# BSPD_SMD.net
KiCad netlist of a schematic drawn in Altium Designer
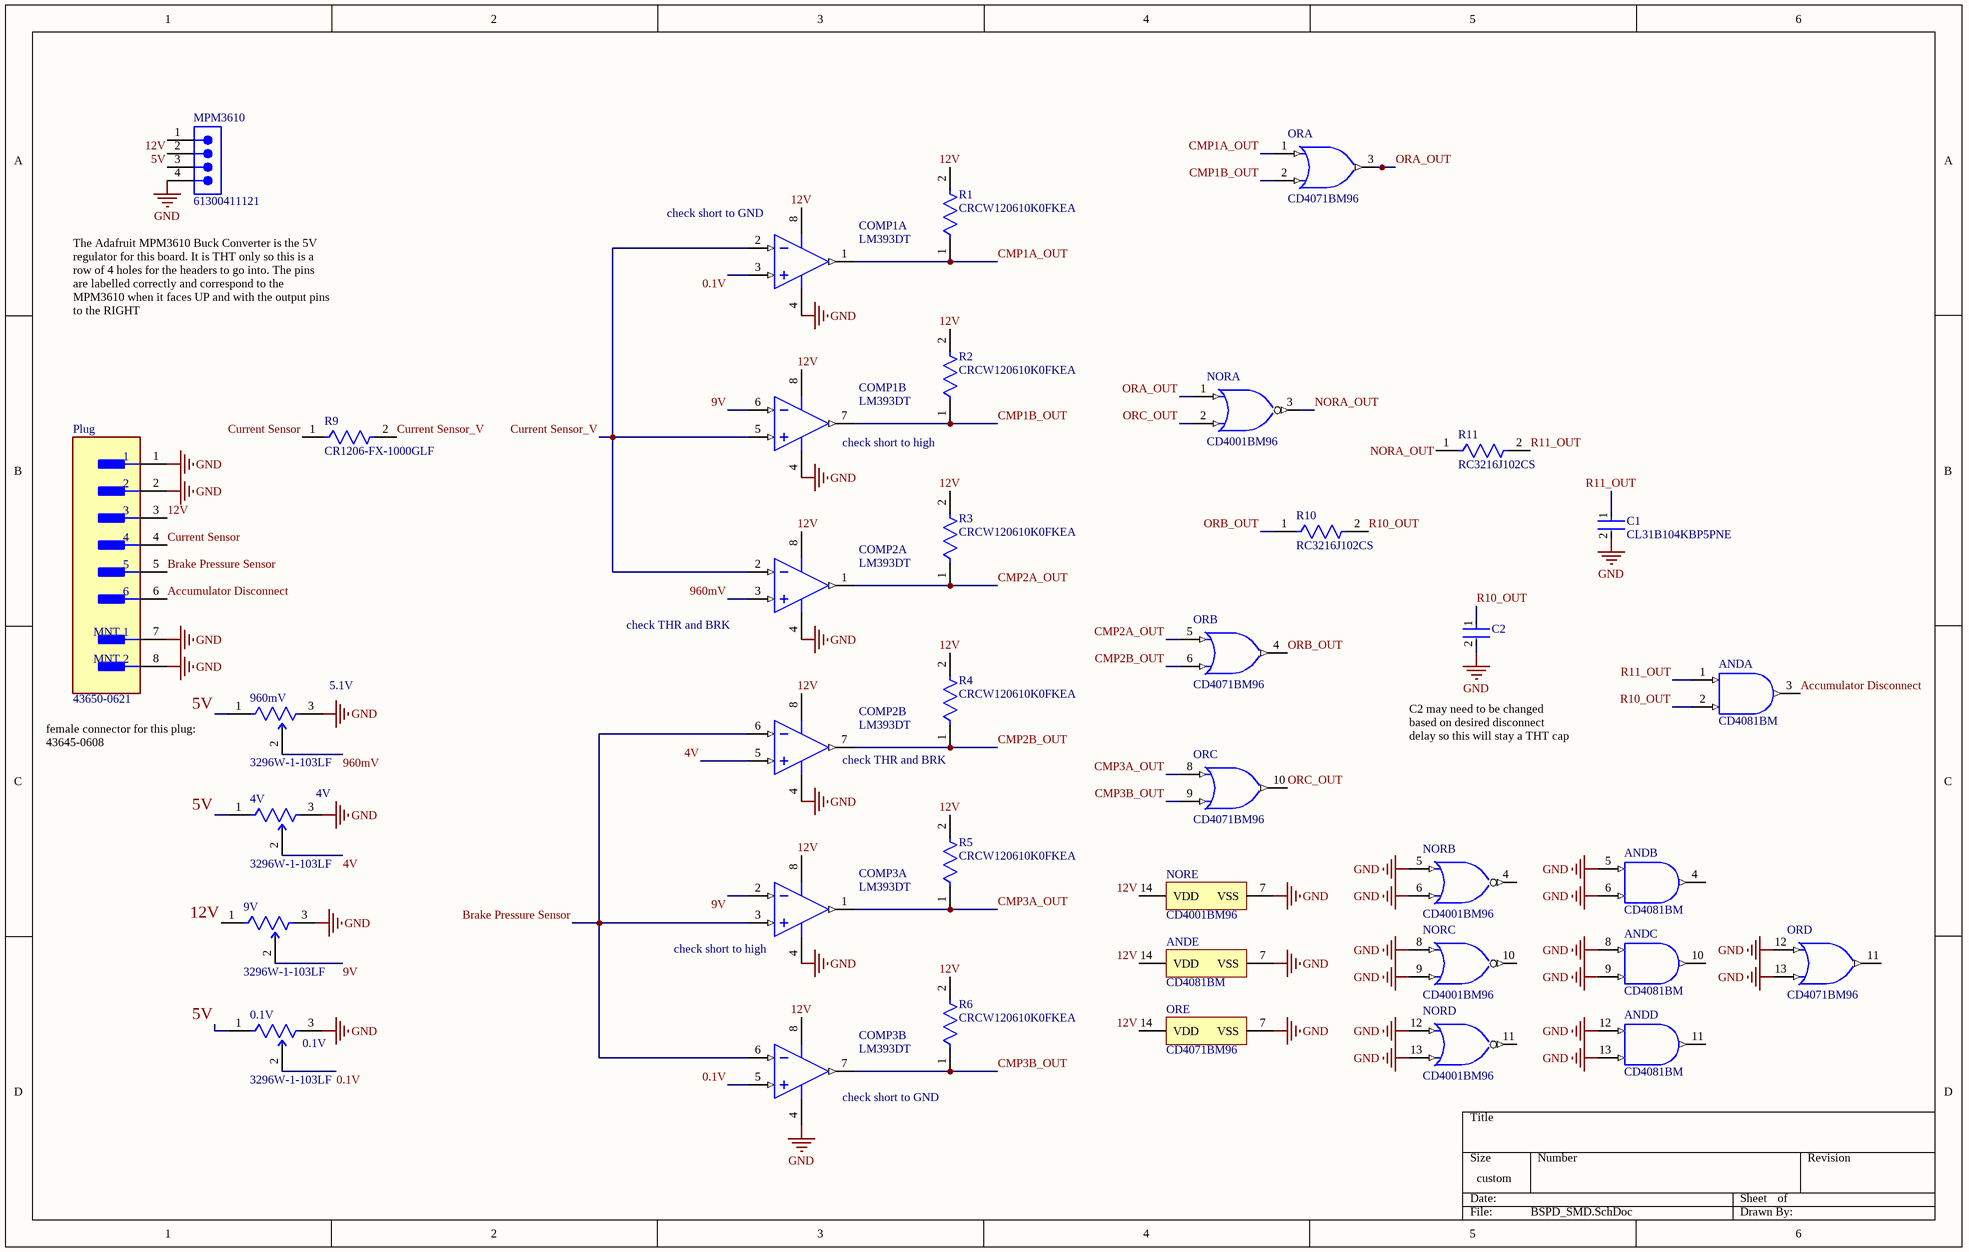
[diagram p0: BSPD_SMD.SchDoc]

(export (version "E")
  (design (tool "Eeschema 10.0.6"))
  (components
    (comp (ref "0.1V")
      (value "3296W-1-103LF")
      (footprint "FP-3296W-MFG")
      (description "TRIMMER 10K OHM 0.5W PC PIN TOP")
      (fields (field (name "TOLERANCE") "10%"))
      (libsource (lib "Altium Content Vault") (part "2dcfd2547301a7d3209a5e99acfd772"))
    )
    (comp (ref "4V")
      (value "3296W-1-103LF")
      (footprint "FP-3296W-MFG")
      (description "TRIMMER 10K OHM 0.5W PC PIN TOP")
      (fields (field (name "TOLERANCE") "10%"))
      (libsource (lib "Altium Content Vault") (part "2dcfd2547301a7d3209a5e99acfd772"))
    )
    (comp (ref "9V")
      (value "3296W-1-103LF")
      (footprint "FP-3296W-MFG")
      (description "TRIMMER 10K OHM 0.5W PC PIN TOP")
      (fields (field (name "TOLERANCE") "10%"))
      (libsource (lib "Altium Content Vault") (part "2dcfd2547301a7d3209a5e99acfd772"))
    )
    (comp (ref "960mV")
      (value "3296W-1-103LF")
      (footprint "FP-3296W-MFG")
      (description "TRIMMER 10K OHM 0.5W PC PIN TOP")
      (fields (field (name "TOLERANCE") "10%"))
      (libsource (lib "Altium Content Vault") (part "2dcfd2547301a7d3209a5e99acfd772"))
    )
    (comp (ref "AND")
      (value "CD4081BM")
      (footprint "D0014A_L")
      (description "CMOS Quad 2-Input AND Gate, D0014A, TUBE")
      (fields
        (field (name "MANUFACTURER") "Texas Instruments")
        (field (name "GENERIC PART NUMBER") "CD4081B")
      )
      (libsource (lib "Altium Content Vault") (part "TI-AND-4-2IN-14_A"))
    )
    (comp (ref "C1")
      (value "CL31B104KBP5PNE")
      (footprint "FP-CL31-IPC_B")
      (description "Cap Ceramic 100nF 50V X7R ±10% SMD 1206 +125°C Embossed T/R")
      (fields (field (name "TOLERANCE") "10%"))
      (libsource (lib "Altium Content Vault") (part "b4654b650e69147ec39a6b967a45e02"))
    )
    (comp (ref "C2")
      (value "RDER71H105K2M1H03A")
      (footprint "FP-RDE2M1-MFG")
      (description "Ceramic Capacitor 1uF ±10% 50V X7R Radial")
      (fields (field (name "TOLERANCE") "10%"))
      (libsource (lib "Altium Content Vault") (part "b4654b650e69147ec39a6b967a45e02"))
    )
    (comp (ref "COMP1")
      (value "LM393DT")
      (footprint "STM-SO-8_D_L")
      (description "Low-Power, Dual-Voltage Comparator, 2 to 36 V, 0 to 70 degC, 8-Pin SOIC (SO), RoHS, Tape and Reel")
      (fields (field (name "MANUFACTURER") "STMicroelectronics"))
      (libsource (lib "Altium Content Vault") (part "STM-LM393-SO8"))
    )
    (comp (ref "COMP2")
      (value "LM393DT")
      (footprint "STM-SO-8_D_L")
      (description "Low-Power, Dual-Voltage Comparator, 2 to 36 V, 0 to 70 degC, 8-Pin SOIC (SO), RoHS, Tape and Reel")
      (fields (field (name "MANUFACTURER") "STMicroelectronics"))
      (libsource (lib "Altium Content Vault") (part "STM-LM393-SO8"))
    )
    (comp (ref "COMP3")
      (value "LM393DT")
      (footprint "STM-SO-8_D_L")
      (description "Low-Power, Dual-Voltage Comparator, 2 to 36 V, 0 to 70 degC, 8-Pin SOIC (SO), RoHS, Tape and Reel")
      (fields (field (name "MANUFACTURER") "STMicroelectronics"))
      (libsource (lib "Altium Content Vault") (part "STM-LM393-SO8"))
    )
    (comp (ref "MPM3610")
      (value "61300411121")
      (footprint "61300411121")
      (libsource (lib "Altium Content Vault") (part "Header_Male_1R_04P"))
    )
    (comp (ref "NOR")
      (value "CD4001BM96")
      (footprint "D0014A_L")
      (description "CMOS Quad 2-Input NOR Gate, D0014A, LARGE T&R")
      (fields
        (field (name "GENERIC PART NUMBER") "CD4001B")
        (field (name "MANUFACTURER") "Texas Instruments")
      )
      (libsource (lib "Altium Content Vault") (part "TI-CD4001B-D0014A-14"))
    )
    (comp (ref "OR")
      (value "CD4071BM96")
      (footprint "D0014A_M")
      (description "CMOS Quad 2-Input OR Gate, D0014A, LARGE T&R")
      (fields
        (field (name "MANUFACTURER") "Texas Instruments")
        (field (name "GENERIC PART NUMBER") "CD4071B")
      )
      (libsource (lib "Altium Content Vault") (part "TI-CD4071B-14"))
    )
    (comp (ref "Plug")
      (value "43650-0621")
      (footprint "FP-43650-0621-MFG")
      (description "43650-0621 Header 3.00mm, SMT, single row, vert, 6w")
      (libsource (lib "Altium Content Vault") (part "ed24c53d9ba001d1a2a686240a95171"))
    )
    (comp (ref "R1")
      (value "CRCW120610K0FKEA")
      (footprint "FP-CRCW1206-e3-IPC_C")
      (description "RES Thick Film, 10kΩ, 1%, 0.25W, 100ppm/°C, 1206")
      (fields (field (name "TOLERANCE") "1%"))
      (libsource (lib "Altium Content Vault") (part "1029c3af85768c4190bb7ad29bc67b5"))
    )
    (comp (ref "R2")
      (value "CRCW120610K0FKEA")
      (footprint "FP-CRCW1206-e3-IPC_C")
      (description "RES Thick Film, 10kΩ, 1%, 0.25W, 100ppm/°C, 1206")
      (fields (field (name "TOLERANCE") "1%"))
      (libsource (lib "Altium Content Vault") (part "1029c3af85768c4190bb7ad29bc67b5"))
    )
    (comp (ref "R3")
      (value "CRCW120610K0FKEA")
      (footprint "FP-CRCW1206-e3-IPC_C")
      (description "RES Thick Film, 10kΩ, 1%, 0.25W, 100ppm/°C, 1206")
      (fields (field (name "TOLERANCE") "1%"))
      (libsource (lib "Altium Content Vault") (part "1029c3af85768c4190bb7ad29bc67b5"))
    )
    (comp (ref "R4")
      (value "CRCW120610K0FKEA")
      (footprint "FP-CRCW1206-e3-IPC_C")
      (description "RES Thick Film, 10kΩ, 1%, 0.25W, 100ppm/°C, 1206")
      (fields (field (name "TOLERANCE") "1%"))
      (libsource (lib "Altium Content Vault") (part "1029c3af85768c4190bb7ad29bc67b5"))
    )
    (comp (ref "R5")
      (value "CRCW120610K0FKEA")
      (footprint "FP-CRCW1206-e3-IPC_C")
      (description "RES Thick Film, 10kΩ, 1%, 0.25W, 100ppm/°C, 1206")
      (fields (field (name "TOLERANCE") "1%"))
      (libsource (lib "Altium Content Vault") (part "1029c3af85768c4190bb7ad29bc67b5"))
    )
    (comp (ref "R6")
      (value "CRCW120610K0FKEA")
      (footprint "FP-CRCW1206-e3-IPC_C")
      (description "RES Thick Film, 10kΩ, 1%, 0.25W, 100ppm/°C, 1206")
      (fields (field (name "TOLERANCE") "1%"))
      (libsource (lib "Altium Content Vault") (part "1029c3af85768c4190bb7ad29bc67b5"))
    )
    (comp (ref "R9")
      (value "CR1206-FX-1000GLF")
      (footprint "FP-CR1206-IPC_A")
      (description "Thick Film Chip Resistors 1206 100Ω 0.25W 1% 100ppm/°C")
      (fields (field (name "TOLERANCE") "1%"))
      (libsource (lib "Altium Content Vault") (part "1029c3af85768c4190bb7ad29bc67b5"))
    )
    (comp (ref "R10")
      (value "RC3216J102CS")
      (footprint "FP-RC3216-MFG")
      (description "Res Thick Film 1206 1kΩ 5% 0.25W ±100ppm/°C Molded SMD T/R")
      (fields (field (name "TOLERANCE") "5%"))
      (libsource (lib "Altium Content Vault") (part "1029c3af85768c4190bb7ad29bc67b5"))
    )
    (comp (ref "R11")
      (value "RC3216J102CS")
      (footprint "FP-RC3216-MFG")
      (description "Res Thick Film 1206 1kΩ 5% 0.25W ±100ppm/°C Molded SMD T/R")
      (fields (field (name "TOLERANCE") "5%"))
      (libsource (lib "Altium Content Vault") (part "1029c3af85768c4190bb7ad29bc67b5"))
    )
  )
  (nets
    (net (code "1") (name "/0.1V") (class "Default")
      (node (ref "0.1V") (pin "2") (pinfunction "WIPER_2") (pintype "passive"))
      (node (ref "COMP1") (pin "3") (pinfunction "IN1+_3") (pintype "input"))
      (node (ref "COMP3") (pin "5") (pinfunction "IN2+_5") (pintype "input"))
    )
    (net (code "2") (name "/4V") (class "Default")
      (node (ref "4V") (pin "2") (pinfunction "WIPER_2") (pintype "passive"))
      (node (ref "COMP2") (pin "5") (pinfunction "IN2+_5") (pintype "input"))
    )
    (net (code "3") (name "/5V") (class "Default")
      (node (ref "0.1V") (pin "1") (pinfunction "CCW_1") (pintype "passive"))
      (node (ref "4V") (pin "1") (pinfunction "CCW_1") (pintype "passive"))
      (node (ref "960mV") (pin "1") (pinfunction "CCW_1") (pintype "passive"))
      (node (ref "MPM3610") (pin "3") (pinfunction "3_3") (pintype "passive"))
    )
    (net (code "4") (name "/9V") (class "Default")
      (node (ref "9V") (pin "2") (pinfunction "WIPER_2") (pintype "passive"))
      (node (ref "COMP1") (pin "6") (pinfunction "IN2-_6") (pintype "input"))
      (node (ref "COMP3") (pin "2") (pinfunction "IN1-_2") (pintype "input"))
    )
    (net (code "5") (name "/12V") (class "Default")
      (node (ref "9V") (pin "1") (pinfunction "CCW_1") (pintype "passive"))
      (node (ref "AND") (pin "14") (pinfunction "VDD_14") (pintype "power_in"))
      (node (ref "COMP1") (pin "8") (pinfunction "VCC+_8") (pintype "power_in"))
      (node (ref "COMP3") (pin "8") (pinfunction "VCC+_8") (pintype "power_in"))
      (node (ref "MPM3610") (pin "2") (pinfunction "2_2") (pintype "passive"))
      (node (ref "NOR") (pin "14") (pinfunction "VDD_14") (pintype "power_in"))
      (node (ref "OR") (pin "14") (pinfunction "VDD_14") (pintype "power_in"))
      (node (ref "Plug") (pin "3") (pinfunction "3_3") (pintype "passive"))
      (node (ref "R1") (pin "2") (pinfunction "2_2") (pintype "passive"))
      (node (ref "R2") (pin "2") (pinfunction "2_2") (pintype "passive"))
      (node (ref "R3") (pin "2") (pinfunction "2_2") (pintype "passive"))
      (node (ref "R4") (pin "2") (pinfunction "2_2") (pintype "passive"))
      (node (ref "R5") (pin "2") (pinfunction "2_2") (pintype "passive"))
      (node (ref "R6") (pin "2") (pinfunction "2_2") (pintype "passive"))
    )
    (net (code "6") (name "/960mV") (class "Default")
      (node (ref "960mV") (pin "2") (pinfunction "WIPER_2") (pintype "passive"))
      (node (ref "COMP2") (pin "3") (pinfunction "IN1+_3") (pintype "input"))
    )
    (net (code "7") (name "/<NO NET>") (class "Default")
      (node (ref "MPM3610") (pin "1") (pinfunction "1_1") (pintype "passive"))
    )
    (net (code "8") (name "/Accumulator Disconnect") (class "Default")
      (node (ref "AND") (pin "3") (pinfunction "J_3") (pintype "output"))
      (node (ref "Plug") (pin "6") (pinfunction "6_6") (pintype "passive"))
    )
    (net (code "9") (name "/Brake Pressure Sensor") (class "Default")
      (node (ref "COMP2") (pin "6") (pinfunction "IN2-_6") (pintype "input"))
      (node (ref "COMP3") (pin "3") (pinfunction "IN1+_3") (pintype "input"))
      (node (ref "COMP3") (pin "6") (pinfunction "IN2-_6") (pintype "input"))
      (node (ref "Plug") (pin "5") (pinfunction "5_5") (pintype "passive"))
    )
    (net (code "10") (name "/CMP1A_OUT") (class "Default")
      (node (ref "COMP1") (pin "1") (pinfunction "OUT1_1") (pintype "output"))
      (node (ref "OR") (pin "1") (pinfunction "A_1") (pintype "input"))
      (node (ref "R1") (pin "1") (pinfunction "1_1") (pintype "passive"))
    )
    (net (code "11") (name "/CMP1B_OUT") (class "Default")
      (node (ref "COMP1") (pin "7") (pinfunction "OUT2_7") (pintype "output"))
      (node (ref "OR") (pin "2") (pinfunction "B_2") (pintype "input"))
      (node (ref "R2") (pin "1") (pinfunction "1_1") (pintype "passive"))
    )
    (net (code "12") (name "/CMP2A_OUT") (class "Default")
      (node (ref "COMP2") (pin "1") (pinfunction "OUT1_1") (pintype "output"))
      (node (ref "OR") (pin "5") (pinfunction "C_5") (pintype "input"))
      (node (ref "R3") (pin "1") (pinfunction "1_1") (pintype "passive"))
    )
    (net (code "13") (name "/CMP2B_OUT") (class "Default")
      (node (ref "COMP2") (pin "7") (pinfunction "OUT2_7") (pintype "output"))
      (node (ref "OR") (pin "6") (pinfunction "D_6") (pintype "input"))
      (node (ref "R4") (pin "1") (pinfunction "1_1") (pintype "passive"))
    )
    (net (code "14") (name "/CMP3A_OUT") (class "Default")
      (node (ref "COMP3") (pin "1") (pinfunction "OUT1_1") (pintype "output"))
      (node (ref "OR") (pin "8") (pinfunction "E_8") (pintype "input"))
      (node (ref "R5") (pin "1") (pinfunction "1_1") (pintype "passive"))
    )
    (net (code "15") (name "/CMP3B_OUT") (class "Default")
      (node (ref "COMP3") (pin "7") (pinfunction "OUT2_7") (pintype "output"))
      (node (ref "OR") (pin "9") (pinfunction "F_9") (pintype "input"))
      (node (ref "R6") (pin "1") (pinfunction "1_1") (pintype "passive"))
    )
    (net (code "16") (name "/Current Sensor") (class "Default")
      (node (ref "Plug") (pin "4") (pinfunction "4_4") (pintype "passive"))
      (node (ref "R9") (pin "1") (pinfunction "1_1") (pintype "passive"))
    )
    (net (code "17") (name "/Current Sensor_V") (class "Default")
      (node (ref "COMP1") (pin "2") (pinfunction "IN1-_2") (pintype "input"))
      (node (ref "COMP1") (pin "5") (pinfunction "IN2+_5") (pintype "input"))
      (node (ref "COMP2") (pin "2") (pinfunction "IN1-_2") (pintype "input"))
      (node (ref "R9") (pin "2") (pinfunction "2_2") (pintype "passive"))
    )
    (net (code "18") (name "/NORA_OUT") (class "Default")
      (node (ref "NOR") (pin "3") (pinfunction "J_3") (pintype "output"))
      (node (ref "R11") (pin "1") (pinfunction "1_1") (pintype "passive"))
    )
    (net (code "19") (name "/ORA_OUT") (class "Default")
      (node (ref "NOR") (pin "1") (pinfunction "A_1") (pintype "input"))
      (node (ref "OR") (pin "3") (pinfunction "J_3") (pintype "output"))
    )
    (net (code "20") (name "/ORB_OUT") (class "Default")
      (node (ref "OR") (pin "4") (pinfunction "K_4") (pintype "output"))
      (node (ref "R10") (pin "1") (pinfunction "1_1") (pintype "passive"))
    )
    (net (code "21") (name "/ORC_OUT") (class "Default")
      (node (ref "NOR") (pin "2") (pinfunction "B_2") (pintype "input"))
      (node (ref "OR") (pin "10") (pinfunction "L_10") (pintype "output"))
    )
    (net (code "22") (name "/R10_OUT") (class "Default")
      (node (ref "AND") (pin "2") (pinfunction "B_2") (pintype "input"))
      (node (ref "C2") (pin "1") (pinfunction "1_1") (pintype "passive"))
      (node (ref "R10") (pin "2") (pinfunction "2_2") (pintype "passive"))
    )
    (net (code "23") (name "/R11_OUT") (class "Default")
      (node (ref "AND") (pin "1") (pinfunction "A_1") (pintype "input"))
      (node (ref "C1") (pin "1") (pinfunction "1_1") (pintype "passive"))
      (node (ref "R11") (pin "2") (pinfunction "2_2") (pintype "passive"))
    )
    (net (code "24") (name "GND") (class "Default")
      (node (ref "0.1V") (pin "3") (pinfunction "CW_3") (pintype "passive"))
      (node (ref "4V") (pin "3") (pinfunction "CW_3") (pintype "passive"))
      (node (ref "960mV") (pin "3") (pinfunction "CW_3") (pintype "passive"))
      (node (ref "9V") (pin "3") (pinfunction "CW_3") (pintype "passive"))
      (node (ref "AND") (pin "12") (pinfunction "G_12") (pintype "input"))
      (node (ref "AND") (pin "13") (pinfunction "H_13") (pintype "input"))
      (node (ref "AND") (pin "5") (pinfunction "C_5") (pintype "input"))
      (node (ref "AND") (pin "6") (pinfunction "D_6") (pintype "input"))
      (node (ref "AND") (pin "7") (pinfunction "VSS_7") (pintype "power_in"))
      (node (ref "AND") (pin "8") (pinfunction "E_8") (pintype "input"))
      (node (ref "AND") (pin "9") (pinfunction "F_9") (pintype "input"))
      (node (ref "C1") (pin "2") (pinfunction "2_2") (pintype "passive"))
      (node (ref "C2") (pin "2") (pinfunction "2_2") (pintype "passive"))
      (node (ref "COMP1") (pin "4") (pinfunction "VCC-_4") (pintype "power_in"))
      (node (ref "COMP2") (pin "4") (pinfunction "VCC-_4") (pintype "power_in"))
      (node (ref "COMP3") (pin "4") (pinfunction "VCC-_4") (pintype "power_in"))
      (node (ref "MPM3610") (pin "4") (pinfunction "4_4") (pintype "passive"))
      (node (ref "NOR") (pin "12") (pinfunction "G_12") (pintype "input"))
      (node (ref "NOR") (pin "13") (pinfunction "H_13") (pintype "input"))
      (node (ref "NOR") (pin "5") (pinfunction "C_5") (pintype "input"))
      (node (ref "NOR") (pin "6") (pinfunction "D_6") (pintype "input"))
      (node (ref "NOR") (pin "7") (pinfunction "VSS_7") (pintype "power_in"))
      (node (ref "NOR") (pin "8") (pinfunction "E_8") (pintype "input"))
      (node (ref "NOR") (pin "9") (pinfunction "F_9") (pintype "input"))
      (node (ref "OR") (pin "12") (pinfunction "G_12") (pintype "input"))
      (node (ref "OR") (pin "13") (pinfunction "H_13") (pintype "input"))
      (node (ref "OR") (pin "7") (pinfunction "VSS_7") (pintype "power_in"))
      (node (ref "Plug") (pin "1") (pinfunction "1_1") (pintype "passive"))
      (node (ref "Plug") (pin "2") (pinfunction "2_2") (pintype "passive"))
      (node (ref "Plug") (pin "7") (pinfunction "MNT_1_7") (pintype "passive"))
      (node (ref "Plug") (pin "8") (pinfunction "MNT_2_8") (pintype "passive"))
    )
    (net (code "25") (name "unconnected-(ANDB-K-Pad4)") (class "Default")
      (node (ref "AND") (pin "4") (pinfunction "K_4") (pintype "output"))
    )
    (net (code "26") (name "unconnected-(ANDC-L-Pad10)") (class "Default")
      (node (ref "AND") (pin "10") (pinfunction "L_10") (pintype "output"))
    )
    (net (code "27") (name "unconnected-(ANDD-M-Pad11)") (class "Default")
      (node (ref "AND") (pin "11") (pinfunction "M_11") (pintype "output"))
    )
    (net (code "28") (name "unconnected-(COMP1B-VCC+-Pad8)") (class "Default")
      (node (ref "COMP1") (pin "8") (pinfunction "VCC+_8") (pintype "power_in"))
    )
    (net (code "29") (name "unconnected-(COMP2A-VCC+-Pad8)") (class "Default")
      (node (ref "COMP2") (pin "8") (pinfunction "VCC+_8") (pintype "power_in"))
    )
    (net (code "30") (name "unconnected-(COMP2B-VCC+-Pad8)") (class "Default")
      (node (ref "COMP2") (pin "8") (pinfunction "VCC+_8") (pintype "power_in"))
    )
    (net (code "31") (name "unconnected-(COMP3A-VCC+-Pad8)") (class "Default")
      (node (ref "COMP3") (pin "8") (pinfunction "VCC+_8") (pintype "power_in"))
    )
    (net (code "32") (name "unconnected-(NORB-K-Pad4)") (class "Default")
      (node (ref "NOR") (pin "4") (pinfunction "K_4") (pintype "output"))
    )
    (net (code "33") (name "unconnected-(NORC-L-Pad10)") (class "Default")
      (node (ref "NOR") (pin "10") (pinfunction "L_10") (pintype "output"))
    )
    (net (code "34") (name "unconnected-(NORD-M-Pad11)") (class "Default")
      (node (ref "NOR") (pin "11") (pinfunction "M_11") (pintype "output"))
    )
    (net (code "35") (name "unconnected-(ORD-M-Pad11)") (class "Default")
      (node (ref "OR") (pin "11") (pinfunction "M_11") (pintype "output"))
    )
  )
)
